# MotorController.net
KiCad netlist of a schematic drawn in Altium Designer
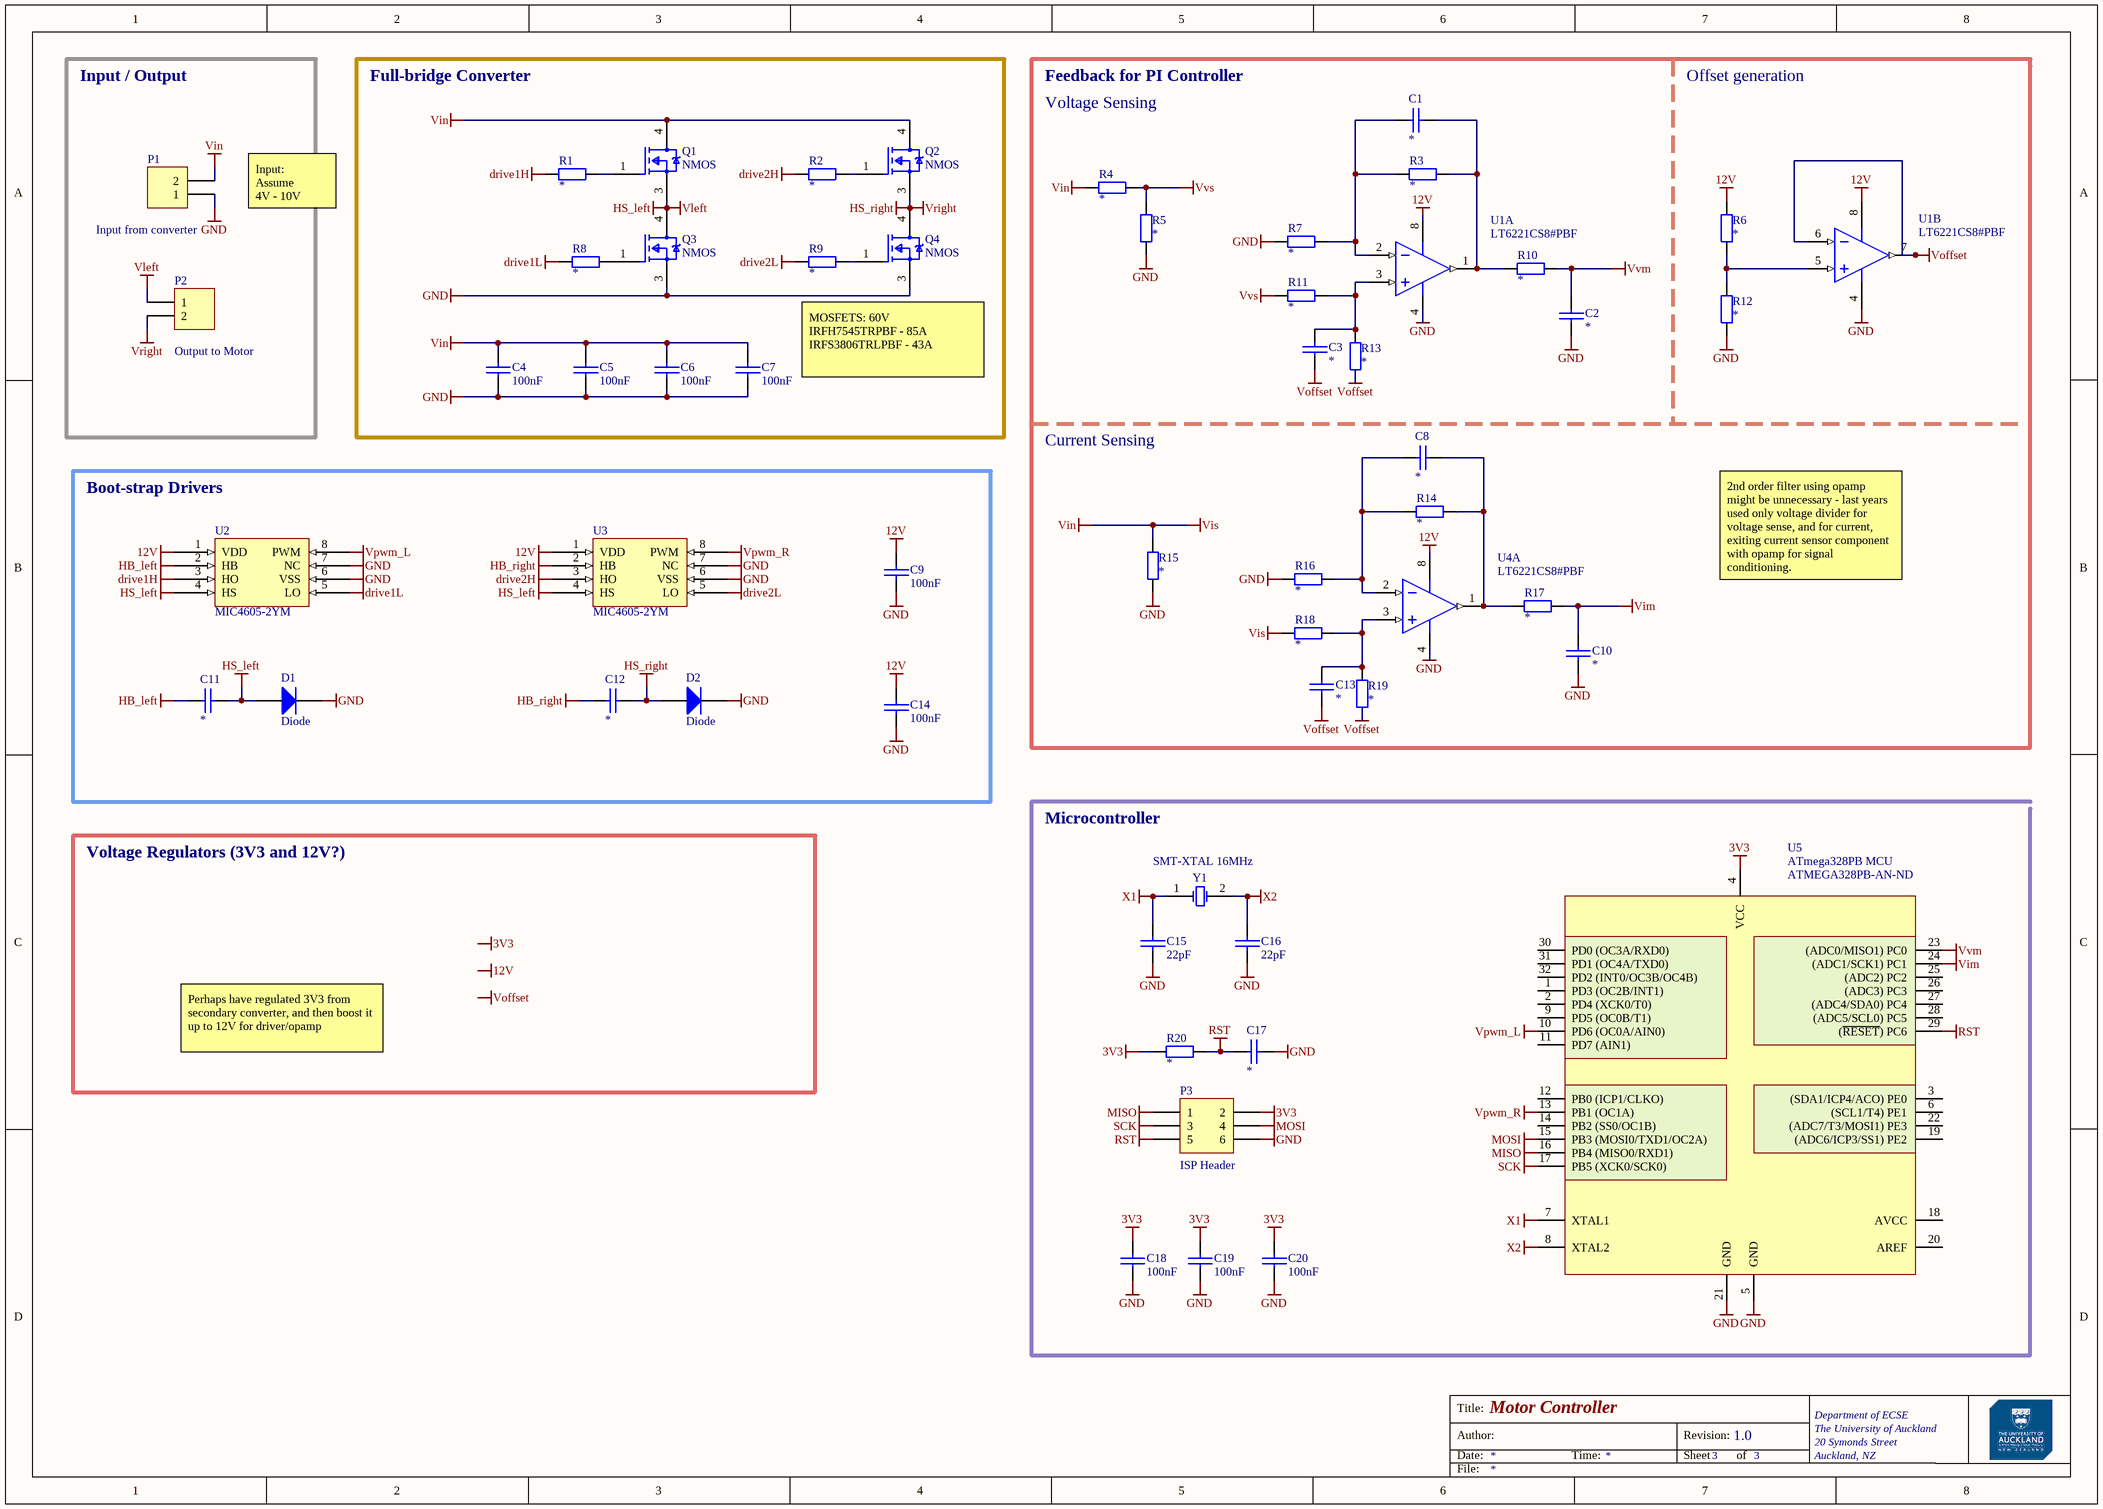
[diagram p0: MotorController.SchDoc]

(export (version "E")
  (design (tool "Eeschema 10.0.6"))
  (components
    (comp (ref "C1")
      (value "*")
      (footprint "0805 CAP")
      (description "SMT ceramic capacitor 0805 size")
      (libsource (lib "EE209_Library") (part "CerCap_SMT_0805"))
    )
    (comp (ref "C2")
      (value "*")
      (footprint "0805 CAP")
      (description "SMT ceramic capacitor 0805 size")
      (libsource (lib "EE209_Library") (part "CerCap_SMT_0805"))
    )
    (comp (ref "C3")
      (value "*")
      (footprint "0805 CAP")
      (description "SMT ceramic capacitor 0805 size")
      (libsource (lib "EE209_Library") (part "CerCap_SMT_0805"))
    )
    (comp (ref "C4")
      (value "100nF")
      (footprint "0805 CAP")
      (description "SMT ceramic capacitor 0805 size")
      (libsource (lib "EE209_Library") (part "CerCap_SMT_0805"))
    )
    (comp (ref "C5")
      (value "100nF")
      (footprint "0805 CAP")
      (description "SMT ceramic capacitor 0805 size")
      (libsource (lib "EE209_Library") (part "CerCap_SMT_0805"))
    )
    (comp (ref "C6")
      (value "100nF")
      (footprint "0805 CAP")
      (description "SMT ceramic capacitor 0805 size")
      (libsource (lib "EE209_Library") (part "CerCap_SMT_0805"))
    )
    (comp (ref "C7")
      (value "100nF")
      (footprint "0805 CAP")
      (description "SMT ceramic capacitor 0805 size")
      (libsource (lib "EE209_Library") (part "CerCap_SMT_0805"))
    )
    (comp (ref "C8")
      (value "*")
      (footprint "0805 CAP")
      (description "SMT ceramic capacitor 0805 size")
      (libsource (lib "EE209_Library") (part "CerCap_SMT_0805"))
    )
    (comp (ref "C9")
      (value "100nF")
      (footprint "0805 CAP")
      (description "SMT ceramic capacitor 0805 size")
      (libsource (lib "EE209_Library") (part "CerCap_SMT_0805"))
    )
    (comp (ref "C10")
      (value "*")
      (footprint "0805 CAP")
      (description "SMT ceramic capacitor 0805 size")
      (libsource (lib "EE209_Library") (part "CerCap_SMT_0805"))
    )
    (comp (ref "C11")
      (value "*")
      (footprint "0805 CAP")
      (description "SMT ceramic capacitor 0805 size")
      (libsource (lib "EE209_Library") (part "CerCap_SMT_0805"))
    )
    (comp (ref "C12")
      (value "*")
      (footprint "0805 CAP")
      (description "SMT ceramic capacitor 0805 size")
      (libsource (lib "EE209_Library") (part "CerCap_SMT_0805"))
    )
    (comp (ref "C13")
      (value "*")
      (footprint "0805 CAP")
      (description "SMT ceramic capacitor 0805 size")
      (libsource (lib "EE209_Library") (part "CerCap_SMT_0805"))
    )
    (comp (ref "C14")
      (value "100nF")
      (footprint "0805 CAP")
      (description "SMT ceramic capacitor 0805 size")
      (libsource (lib "EE209_Library") (part "CerCap_SMT_0805"))
    )
    (comp (ref "C15")
      (value "22pF")
      (footprint "0805 CAP")
      (description "SMT ceramic capacitor 0805 size")
      (libsource (lib "EE209_Library") (part "CerCap_SMT_0805"))
    )
    (comp (ref "C16")
      (value "22pF")
      (footprint "0805 CAP")
      (description "SMT ceramic capacitor 0805 size")
      (libsource (lib "EE209_Library") (part "CerCap_SMT_0805"))
    )
    (comp (ref "C17")
      (value "*")
      (footprint "0805 CAP")
      (description "SMT ceramic capacitor 0805 size")
      (libsource (lib "EE209_Library") (part "CerCap_SMT_0805"))
    )
    (comp (ref "C18")
      (value "100nF")
      (footprint "0805 CAP")
      (description "SMT ceramic capacitor 0805 size")
      (libsource (lib "EE209_Library") (part "CerCap_SMT_0805"))
    )
    (comp (ref "C19")
      (value "100nF")
      (footprint "0805 CAP")
      (description "SMT ceramic capacitor 0805 size")
      (libsource (lib "EE209_Library") (part "CerCap_SMT_0805"))
    )
    (comp (ref "C20")
      (value "100nF")
      (footprint "0805 CAP")
      (description "SMT ceramic capacitor 0805 size")
      (libsource (lib "EE209_Library") (part "CerCap_SMT_0805"))
    )
    (comp (ref "D1")
      (value "Diode")
      (footprint "SMC")
      (description "Default Diode")
      (fields (field (name "PUBLISHER") "Altium Limited"))
      (libsource (lib "Miscellaneous Devices") (part "Diode"))
    )
    (comp (ref "D2")
      (value "Diode")
      (footprint "SMC")
      (description "Default Diode")
      (fields (field (name "PUBLISHER") "Altium Limited"))
      (libsource (lib "Miscellaneous Devices") (part "Diode"))
    )
    (comp (ref "P1")
      (value "Input from converter")
      (footprint "HDR1X2H")
      (description "Header, 2-Pin, Right Angle")
      (fields (field (name "PUBLISHER") "Altium Limited"))
      (libsource (lib "Miscellaneous Connectors") (part "Header 2H"))
    )
    (comp (ref "P2")
      (value "Output to Motor")
      (footprint "HDR1X2H")
      (description "Header, 2-Pin, Right Angle")
      (fields (field (name "PUBLISHER") "Altium Limited"))
      (libsource (lib "") (part "Header 2H_1"))
    )
    (comp (ref "P3")
      (value "ISP Header")
      (footprint "HDR2X3")
      (description "Header, 3-Pin, Dual row")
      (fields (field (name "PUBLISHER") "Altium Limited"))
      (libsource (lib "Miscellaneous Connectors") (part "Header 3X2"))
    )
    (comp (ref "Q1")
      (value "NMOS")
      (footprint "IRFS3806TRLPBFCT-ND")
      (description "Single N-Channel 60V 15.8 mOhm 22 nC HEXFET® Power Mosfet - D2PAK")
      (fields
        (field (name "MANUFACTURER") "Infineon")
        (field (name "MANUFACTURER PART NUMBER") "IRFS3806TRLPBF")
      )
      (libsource (lib "SummerWorkshop") (part "NMOS"))
    )
    (comp (ref "Q2")
      (value "NMOS")
      (footprint "IRFS3806TRLPBFCT-ND")
      (description "Single N-Channel 60V 15.8 mOhm 22 nC HEXFET® Power Mosfet - D2PAK")
      (fields
        (field (name "MANUFACTURER") "Infineon")
        (field (name "MANUFACTURER PART NUMBER") "IRFS3806TRLPBF")
      )
      (libsource (lib "SummerWorkshop") (part "NMOS"))
    )
    (comp (ref "Q3")
      (value "NMOS")
      (footprint "IRFS3806TRLPBFCT-ND")
      (description "Single N-Channel 60V 15.8 mOhm 22 nC HEXFET® Power Mosfet - D2PAK")
      (fields
        (field (name "MANUFACTURER") "Infineon")
        (field (name "MANUFACTURER PART NUMBER") "IRFS3806TRLPBF")
      )
      (libsource (lib "SummerWorkshop") (part "NMOS"))
    )
    (comp (ref "Q4")
      (value "NMOS")
      (footprint "IRFS3806TRLPBFCT-ND")
      (description "Single N-Channel 60V 15.8 mOhm 22 nC HEXFET® Power Mosfet - D2PAK")
      (fields
        (field (name "MANUFACTURER") "Infineon")
        (field (name "MANUFACTURER PART NUMBER") "IRFS3806TRLPBF")
      )
      (libsource (lib "SummerWorkshop") (part "NMOS"))
    )
    (comp (ref "R1")
      (value "*")
      (footprint "0805 RES")
      (description "0805 resistor")
      (fields (field (name "PUBLISHER") "Altium Limited"))
      (libsource (lib "EE209_Library") (part "Res_SMT_0805"))
    )
    (comp (ref "R2")
      (value "*")
      (footprint "0805 RES")
      (description "0805 resistor")
      (fields (field (name "PUBLISHER") "Altium Limited"))
      (libsource (lib "EE209_Library") (part "Res_SMT_0805"))
    )
    (comp (ref "R3")
      (value "*")
      (footprint "0805 RES")
      (description "0805 resistor")
      (fields (field (name "PUBLISHER") "Altium Limited"))
      (libsource (lib "") (part "Res_SMT_0805_2"))
    )
    (comp (ref "R4")
      (value "*")
      (footprint "0805 RES")
      (description "0805 resistor")
      (fields (field (name "PUBLISHER") "Altium Limited"))
      (libsource (lib "") (part "Res_SMT_0805_2"))
    )
    (comp (ref "R5")
      (value "*")
      (footprint "0805 RES")
      (description "0805 resistor")
      (fields (field (name "PUBLISHER") "Altium Limited"))
      (libsource (lib "") (part "Res_SMT_0805_3"))
    )
    (comp (ref "R6")
      (value "*")
      (footprint "0805 RES")
      (description "0805 resistor")
      (fields (field (name "PUBLISHER") "Altium Limited"))
      (libsource (lib "") (part "Res_SMT_0805_1"))
    )
    (comp (ref "R7")
      (value "*")
      (footprint "0805 RES")
      (description "0805 resistor")
      (fields (field (name "PUBLISHER") "Altium Limited"))
      (libsource (lib "EE209_Library") (part "Res_SMT_0805"))
    )
    (comp (ref "R8")
      (value "*")
      (footprint "0805 RES")
      (description "0805 resistor")
      (fields (field (name "PUBLISHER") "Altium Limited"))
      (libsource (lib "EE209_Library") (part "Res_SMT_0805"))
    )
    (comp (ref "R9")
      (value "*")
      (footprint "0805 RES")
      (description "0805 resistor")
      (fields (field (name "PUBLISHER") "Altium Limited"))
      (libsource (lib "EE209_Library") (part "Res_SMT_0805"))
    )
    (comp (ref "R10")
      (value "*")
      (footprint "0805 RES")
      (description "0805 resistor")
      (fields (field (name "PUBLISHER") "Altium Limited"))
      (libsource (lib "") (part "Res_SMT_0805_2"))
    )
    (comp (ref "R11")
      (value "*")
      (footprint "0805 RES")
      (description "0805 resistor")
      (fields (field (name "PUBLISHER") "Altium Limited"))
      (libsource (lib "EE209_Library") (part "Res_SMT_0805"))
    )
    (comp (ref "R12")
      (value "*")
      (footprint "0805 RES")
      (description "0805 resistor")
      (fields (field (name "PUBLISHER") "Altium Limited"))
      (libsource (lib "") (part "Res_SMT_0805_1"))
    )
    (comp (ref "R13")
      (value "*")
      (footprint "0805 RES")
      (description "0805 resistor")
      (fields (field (name "PUBLISHER") "Altium Limited"))
      (libsource (lib "") (part "Res_SMT_0805_1"))
    )
    (comp (ref "R14")
      (value "*")
      (footprint "0805 RES")
      (description "0805 resistor")
      (fields (field (name "PUBLISHER") "Altium Limited"))
      (libsource (lib "") (part "Res_SMT_0805_2"))
    )
    (comp (ref "R15")
      (value "*")
      (footprint "0805 RES")
      (description "0805 resistor")
      (fields (field (name "PUBLISHER") "Altium Limited"))
      (libsource (lib "") (part "Res_SMT_0805_3"))
    )
    (comp (ref "R16")
      (value "*")
      (footprint "0805 RES")
      (description "0805 resistor")
      (fields (field (name "PUBLISHER") "Altium Limited"))
      (libsource (lib "EE209_Library") (part "Res_SMT_0805"))
    )
    (comp (ref "R17")
      (value "*")
      (footprint "0805 RES")
      (description "0805 resistor")
      (fields (field (name "PUBLISHER") "Altium Limited"))
      (libsource (lib "") (part "Res_SMT_0805_2"))
    )
    (comp (ref "R18")
      (value "*")
      (footprint "0805 RES")
      (description "0805 resistor")
      (fields (field (name "PUBLISHER") "Altium Limited"))
      (libsource (lib "EE209_Library") (part "Res_SMT_0805"))
    )
    (comp (ref "R19")
      (value "*")
      (footprint "0805 RES")
      (description "0805 resistor")
      (fields (field (name "PUBLISHER") "Altium Limited"))
      (libsource (lib "") (part "Res_SMT_0805_1"))
    )
    (comp (ref "R20")
      (value "*")
      (footprint "0805 RES")
      (description "0805 resistor")
      (fields (field (name "PUBLISHER") "Altium Limited"))
      (libsource (lib "") (part "Res_SMT_0805_2"))
    )
    (comp (ref "U1")
      (value "LT6221CS8#PBF")
      (footprint "LT-S8-8_N")
      (fields
        (field (name "LINEAR TECHNOLOGY PART NUMBER") "LT6221")
        (field (name "MANUFACTURER") "Linear Technology")
      )
      (libsource (lib "Altium Content Vault") (part "LT-LT6221-S8-8"))
    )
    (comp (ref "U2")
      (value "MIC4605-2YM")
      (description "Driver 1A 2-OUT High and Low Side Half Brdg Non-Inv 8-Pin SOIC N Tube")
      (fields
        (field (name "MANUFACTURER") "Microchip")
        (field (name "MANUFACTURER PART NUMBER") "MIC4605-2YM-T5")
      )
      (libsource (lib "SummerWorkshop") (part "MIC4605-2YM"))
    )
    (comp (ref "U3")
      (value "MIC4605-2YM")
      (description "Driver 1A 2-OUT High and Low Side Half Brdg Non-Inv 8-Pin SOIC N Tube")
      (fields
        (field (name "MANUFACTURER") "Microchip")
        (field (name "MANUFACTURER PART NUMBER") "MIC4605-2YM-T5")
      )
      (libsource (lib "SummerWorkshop") (part "MIC4605-2YM"))
    )
    (comp (ref "U4")
      (value "LT6221CS8#PBF")
      (footprint "LT-S8-8_N")
      (fields
        (field (name "LINEAR TECHNOLOGY PART NUMBER") "LT6221")
        (field (name "MANUFACTURER") "Linear Technology")
      )
      (libsource (lib "Altium Content Vault") (part "LT-LT6221-S8-8"))
    )
    (comp (ref "U5")
      (value "ATmega328PB MCU")
      (footprint "32 - TQFP")
      (description "IC MCU 8BIT 32KB FLASH 32TQFP")
      (fields
        (field (name "MANUFACTURER") "Atmel")
        (field (name "MANUFACTURER PART NUMBER") "ATMEGA328PB-AN")
        (field (name "SUPPLIER PART NUMBER 1") "ATMEGA328PB-AN-ND")
      )
      (libsource (lib "EE209_Library") (part "ATmega328PB_SMT_TQFP32"))
    )
    (comp (ref "Y1")
      (value "SMT-XTAL 16MHz")
      (footprint "HC49-US")
      (description "9C-16.000MAAJ-T crystal 16.0000MHZ 18PF SMD")
      (fields
        (field (name "MANUFACTURER") "TXC CORPORATION")
        (field (name "MANUFACTURER PART NUMBER") "9C-16.000MAAJ-T")
      )
      (libsource (lib "EE209_Library") (part "TXC9C-16_XTAL_SMT"))
    )
  )
  (nets
    (net (code "1") (name "3V3") (class "Default")
      (node (ref "C18") (pin "1") (pinfunction "1_1") (pintype "passive"))
      (node (ref "C19") (pin "1") (pinfunction "1_1") (pintype "passive"))
      (node (ref "C20") (pin "1") (pinfunction "1_1") (pintype "passive"))
      (node (ref "P3") (pin "2") (pinfunction "2_2") (pintype "passive"))
      (node (ref "R20") (pin "2") (pinfunction "2_2") (pintype "passive"))
      (node (ref "U5") (pin "4") (pinfunction "VCC_4") (pintype "passive"))
    )
    (net (code "2") (name "12V") (class "Default")
      (node (ref "C14") (pin "2") (pinfunction "2_2") (pintype "passive"))
      (node (ref "C9") (pin "2") (pinfunction "2_2") (pintype "passive"))
      (node (ref "R6") (pin "2") (pinfunction "2_2") (pintype "passive"))
      (node (ref "U1") (pin "8") (pinfunction "VS+_8") (pintype "power_in"))
      (node (ref "U2") (pin "1") (pinfunction "VDD_1") (pintype "input"))
      (node (ref "U3") (pin "1") (pinfunction "VDD_1") (pintype "input"))
      (node (ref "U4") (pin "8") (pinfunction "VS+_8") (pintype "power_in"))
    )
    (net (code "3") (name "GND") (class "Default")
      (node (ref "C10") (pin "1") (pinfunction "1_1") (pintype "passive"))
      (node (ref "C14") (pin "1") (pinfunction "1_1") (pintype "passive"))
      (node (ref "C15") (pin "2") (pinfunction "2_2") (pintype "passive"))
      (node (ref "C16") (pin "2") (pinfunction "2_2") (pintype "passive"))
      (node (ref "C17") (pin "2") (pinfunction "2_2") (pintype "passive"))
      (node (ref "C18") (pin "2") (pinfunction "2_2") (pintype "passive"))
      (node (ref "C19") (pin "2") (pinfunction "2_2") (pintype "passive"))
      (node (ref "C2") (pin "1") (pinfunction "1_1") (pintype "passive"))
      (node (ref "C20") (pin "2") (pinfunction "2_2") (pintype "passive"))
      (node (ref "C4") (pin "1") (pinfunction "1_1") (pintype "passive"))
      (node (ref "C5") (pin "1") (pinfunction "1_1") (pintype "passive"))
      (node (ref "C6") (pin "1") (pinfunction "1_1") (pintype "passive"))
      (node (ref "C7") (pin "1") (pinfunction "1_1") (pintype "passive"))
      (node (ref "C9") (pin "1") (pinfunction "1_1") (pintype "passive"))
      (node (ref "D1") (pin "2") (pinfunction "K_2") (pintype "passive"))
      (node (ref "D2") (pin "2") (pinfunction "K_2") (pintype "passive"))
      (node (ref "P1") (pin "1") (pinfunction "1_1") (pintype "passive"))
      (node (ref "P3") (pin "6") (pinfunction "6_6") (pintype "passive"))
      (node (ref "Q3") (pin "3") (pinfunction "S_3") (pintype "passive"))
      (node (ref "Q4") (pin "3") (pinfunction "S_3") (pintype "passive"))
      (node (ref "R12") (pin "1") (pinfunction "1_1") (pintype "passive"))
      (node (ref "R15") (pin "2") (pinfunction "2_2") (pintype "passive"))
      (node (ref "R16") (pin "1") (pinfunction "1_1") (pintype "passive"))
      (node (ref "R5") (pin "2") (pinfunction "2_2") (pintype "passive"))
      (node (ref "R7") (pin "1") (pinfunction "1_1") (pintype "passive"))
      (node (ref "U1") (pin "4") (pinfunction "VS-_4") (pintype "power_in"))
      (node (ref "U2") (pin "6") (pinfunction "VSS_6") (pintype "input"))
      (node (ref "U2") (pin "7") (pinfunction "NC_7") (pintype "input"))
      (node (ref "U3") (pin "6") (pinfunction "VSS_6") (pintype "input"))
      (node (ref "U3") (pin "7") (pinfunction "NC_7") (pintype "input"))
      (node (ref "U4") (pin "4") (pinfunction "VS-_4") (pintype "power_in"))
      (node (ref "U5") (pin "21") (pinfunction "GND_21") (pintype "passive"))
      (node (ref "U5") (pin "5") (pinfunction "GND_5") (pintype "passive"))
    )
    (net (code "4") (name "HB_left") (class "Default")
      (node (ref "C11") (pin "1") (pinfunction "1_1") (pintype "passive"))
      (node (ref "U2") (pin "2") (pinfunction "HB_2") (pintype "input"))
    )
    (net (code "5") (name "HB_right") (class "Default")
      (node (ref "C12") (pin "1") (pinfunction "1_1") (pintype "passive"))
      (node (ref "U3") (pin "2") (pinfunction "HB_2") (pintype "input"))
    )
    (net (code "6") (name "HS_left") (class "Default")
      (node (ref "C11") (pin "2") (pinfunction "2_2") (pintype "passive"))
      (node (ref "D1") (pin "1") (pinfunction "A_1") (pintype "passive"))
      (node (ref "P2") (pin "1") (pinfunction "1_1") (pintype "passive"))
      (node (ref "Q1") (pin "3") (pinfunction "S_3") (pintype "passive"))
      (node (ref "Q3") (pin "4") (pinfunction "D_4") (pintype "passive"))
      (node (ref "U2") (pin "4") (pinfunction "HS_4") (pintype "input"))
      (node (ref "U3") (pin "4") (pinfunction "HS_4") (pintype "input"))
    )
    (net (code "7") (name "HS_right") (class "Default")
      (node (ref "C12") (pin "2") (pinfunction "2_2") (pintype "passive"))
      (node (ref "D2") (pin "1") (pinfunction "A_1") (pintype "passive"))
      (node (ref "P2") (pin "2") (pinfunction "2_2") (pintype "passive"))
      (node (ref "Q2") (pin "3") (pinfunction "S_3") (pintype "passive"))
      (node (ref "Q4") (pin "4") (pinfunction "D_4") (pintype "passive"))
    )
    (net (code "8") (name "MISO") (class "Default")
      (node (ref "P3") (pin "1") (pinfunction "1_1") (pintype "passive"))
      (node (ref "U5") (pin "16") (pinfunction "PB4_(MISO0/RXD1)_16") (pintype "passive"))
    )
    (net (code "9") (name "MOSI") (class "Default")
      (node (ref "P3") (pin "4") (pinfunction "4_4") (pintype "passive"))
      (node (ref "U5") (pin "15") (pinfunction "PB3_(MOSI0/TXD1/OC2A)_15") (pintype "passive"))
    )
    (net (code "10") (name "Net-(Q1-G)") (class "Default")
      (node (ref "Q1") (pin "1") (pinfunction "G_1") (pintype "passive"))
      (node (ref "R1") (pin "2") (pinfunction "2_2") (pintype "passive"))
    )
    (net (code "11") (name "Net-(Q2-G)") (class "Default")
      (node (ref "Q2") (pin "1") (pinfunction "G_1") (pintype "passive"))
      (node (ref "R2") (pin "2") (pinfunction "2_2") (pintype "passive"))
    )
    (net (code "12") (name "Net-(Q3-G)") (class "Default")
      (node (ref "Q3") (pin "1") (pinfunction "G_1") (pintype "passive"))
      (node (ref "R8") (pin "2") (pinfunction "2_2") (pintype "passive"))
    )
    (net (code "13") (name "Net-(Q4-G)") (class "Default")
      (node (ref "Q4") (pin "1") (pinfunction "G_1") (pintype "passive"))
      (node (ref "R9") (pin "2") (pinfunction "2_2") (pintype "passive"))
    )
    (net (code "14") (name "Net-(U1A-+IN_A)") (class "Default")
      (node (ref "C3") (pin "2") (pinfunction "2_2") (pintype "passive"))
      (node (ref "R11") (pin "2") (pinfunction "2_2") (pintype "passive"))
      (node (ref "R13") (pin "2") (pinfunction "2_2") (pintype "passive"))
      (node (ref "U1") (pin "3") (pinfunction "+IN_A_3") (pintype "input"))
    )
    (net (code "15") (name "Net-(U1A--IN_A)") (class "Default")
      (node (ref "C1") (pin "1") (pinfunction "1_1") (pintype "passive"))
      (node (ref "R3") (pin "2") (pinfunction "2_2") (pintype "passive"))
      (node (ref "R7") (pin "2") (pinfunction "2_2") (pintype "passive"))
      (node (ref "U1") (pin "2") (pinfunction "-IN_A_2") (pintype "input"))
    )
    (net (code "16") (name "Net-(U1A-OUT_A)") (class "Default")
      (node (ref "C1") (pin "2") (pinfunction "2_2") (pintype "passive"))
      (node (ref "R10") (pin "2") (pinfunction "2_2") (pintype "passive"))
      (node (ref "R3") (pin "1") (pinfunction "1_1") (pintype "passive"))
      (node (ref "U1") (pin "1") (pinfunction "OUT_A_1") (pintype "output"))
    )
    (net (code "17") (name "Net-(U1B-+IN_B)") (class "Default")
      (node (ref "R12") (pin "2") (pinfunction "2_2") (pintype "passive"))
      (node (ref "R6") (pin "1") (pinfunction "1_1") (pintype "passive"))
      (node (ref "U1") (pin "5") (pinfunction "+IN_B_5") (pintype "input"))
    )
    (net (code "18") (name "Net-(U4A-+IN_A)") (class "Default")
      (node (ref "C13") (pin "2") (pinfunction "2_2") (pintype "passive"))
      (node (ref "R18") (pin "2") (pinfunction "2_2") (pintype "passive"))
      (node (ref "R19") (pin "2") (pinfunction "2_2") (pintype "passive"))
      (node (ref "U4") (pin "3") (pinfunction "+IN_A_3") (pintype "input"))
    )
    (net (code "19") (name "Net-(U4A--IN_A)") (class "Default")
      (node (ref "C8") (pin "1") (pinfunction "1_1") (pintype "passive"))
      (node (ref "R14") (pin "2") (pinfunction "2_2") (pintype "passive"))
      (node (ref "R16") (pin "2") (pinfunction "2_2") (pintype "passive"))
      (node (ref "U4") (pin "2") (pinfunction "-IN_A_2") (pintype "input"))
    )
    (net (code "20") (name "Net-(U4A-OUT_A)") (class "Default")
      (node (ref "C8") (pin "2") (pinfunction "2_2") (pintype "passive"))
      (node (ref "R14") (pin "1") (pinfunction "1_1") (pintype "passive"))
      (node (ref "R17") (pin "2") (pinfunction "2_2") (pintype "passive"))
      (node (ref "U4") (pin "1") (pinfunction "OUT_A_1") (pintype "output"))
    )
    (net (code "21") (name "RST") (class "Default")
      (node (ref "C17") (pin "1") (pinfunction "1_1") (pintype "passive"))
      (node (ref "P3") (pin "5") (pinfunction "5_5") (pintype "passive"))
      (node (ref "R20") (pin "1") (pinfunction "1_1") (pintype "passive"))
      (node (ref "U5") (pin "29") (pinfunction "(~{RESET})_PC6_29") (pintype "passive"))
    )
    (net (code "22") (name "SCK") (class "Default")
      (node (ref "P3") (pin "3") (pinfunction "3_3") (pintype "passive"))
      (node (ref "U5") (pin "17") (pinfunction "PB5_(XCK0/SCK0)_17") (pintype "passive"))
    )
    (net (code "23") (name "Vim") (class "Default")
      (node (ref "C10") (pin "2") (pinfunction "2_2") (pintype "passive"))
      (node (ref "R17") (pin "1") (pinfunction "1_1") (pintype "passive"))
      (node (ref "U5") (pin "24") (pinfunction "(ADC1/SCK1)_PC1_24") (pintype "passive"))
    )
    (net (code "24") (name "Vin") (class "Default")
      (node (ref "C4") (pin "2") (pinfunction "2_2") (pintype "passive"))
      (node (ref "C5") (pin "2") (pinfunction "2_2") (pintype "passive"))
      (node (ref "C6") (pin "2") (pinfunction "2_2") (pintype "passive"))
      (node (ref "C7") (pin "2") (pinfunction "2_2") (pintype "passive"))
      (node (ref "P1") (pin "2") (pinfunction "2_2") (pintype "passive"))
      (node (ref "Q1") (pin "4") (pinfunction "D_4") (pintype "passive"))
      (node (ref "Q2") (pin "4") (pinfunction "D_4") (pintype "passive"))
      (node (ref "R15") (pin "1") (pinfunction "1_1") (pintype "passive"))
      (node (ref "R18") (pin "1") (pinfunction "1_1") (pintype "passive"))
      (node (ref "R4") (pin "2") (pinfunction "2_2") (pintype "passive"))
    )
    (net (code "25") (name "Voffset") (class "Default")
      (node (ref "C13") (pin "1") (pinfunction "1_1") (pintype "passive"))
      (node (ref "C3") (pin "1") (pinfunction "1_1") (pintype "passive"))
      (node (ref "R13") (pin "1") (pinfunction "1_1") (pintype "passive"))
      (node (ref "R19") (pin "1") (pinfunction "1_1") (pintype "passive"))
      (node (ref "U1") (pin "6") (pinfunction "-IN_B_6") (pintype "input"))
      (node (ref "U1") (pin "7") (pinfunction "OUT_B_7") (pintype "output"))
    )
    (net (code "26") (name "Vpwm_L") (class "Default")
      (node (ref "U2") (pin "8") (pinfunction "PWM_8") (pintype "input"))
      (node (ref "U5") (pin "10") (pinfunction "PD6_(OC0A/AIN0)_10") (pintype "passive"))
    )
    (net (code "27") (name "Vpwm_R") (class "Default")
      (node (ref "U3") (pin "8") (pinfunction "PWM_8") (pintype "input"))
      (node (ref "U5") (pin "13") (pinfunction "PB1_(OC1A)_13") (pintype "passive"))
    )
    (net (code "28") (name "Vvm") (class "Default")
      (node (ref "C2") (pin "2") (pinfunction "2_2") (pintype "passive"))
      (node (ref "R10") (pin "1") (pinfunction "1_1") (pintype "passive"))
      (node (ref "U5") (pin "23") (pinfunction "(ADC0/MISO1)_PC0_23") (pintype "passive"))
    )
    (net (code "29") (name "Vvs") (class "Default")
      (node (ref "R11") (pin "1") (pinfunction "1_1") (pintype "passive"))
      (node (ref "R4") (pin "1") (pinfunction "1_1") (pintype "passive"))
      (node (ref "R5") (pin "1") (pinfunction "1_1") (pintype "passive"))
    )
    (net (code "30") (name "X1") (class "Default")
      (node (ref "C15") (pin "1") (pinfunction "1_1") (pintype "passive"))
      (node (ref "U5") (pin "7") (pinfunction "XTAL1_7") (pintype "passive"))
      (node (ref "Y1") (pin "1") (pinfunction "OSC1_1") (pintype "passive"))
    )
    (net (code "31") (name "X2") (class "Default")
      (node (ref "C16") (pin "1") (pinfunction "1_1") (pintype "passive"))
      (node (ref "U5") (pin "8") (pinfunction "XTAL2_8") (pintype "passive"))
      (node (ref "Y1") (pin "2") (pinfunction "OSC2_2") (pintype "passive"))
    )
    (net (code "32") (name "drive1H") (class "Default")
      (node (ref "R1") (pin "1") (pinfunction "1_1") (pintype "passive"))
      (node (ref "U2") (pin "3") (pinfunction "HO_3") (pintype "input"))
    )
    (net (code "33") (name "drive1L") (class "Default")
      (node (ref "R8") (pin "1") (pinfunction "1_1") (pintype "passive"))
      (node (ref "U2") (pin "5") (pinfunction "LO_5") (pintype "input"))
    )
    (net (code "34") (name "drive2H") (class "Default")
      (node (ref "R2") (pin "1") (pinfunction "1_1") (pintype "passive"))
      (node (ref "U3") (pin "3") (pinfunction "HO_3") (pintype "input"))
    )
    (net (code "35") (name "drive2L") (class "Default")
      (node (ref "R9") (pin "1") (pinfunction "1_1") (pintype "passive"))
      (node (ref "U3") (pin "5") (pinfunction "LO_5") (pintype "input"))
    )
    (net (code "36") (name "unconnected-(U5-(ADC2)_PC2-Pad25)") (class "Default")
      (node (ref "U5") (pin "25") (pinfunction "(ADC2)_PC2_25") (pintype "passive"))
    )
    (net (code "37") (name "unconnected-(U5-(ADC3)_PC3-Pad26)") (class "Default")
      (node (ref "U5") (pin "26") (pinfunction "(ADC3)_PC3_26") (pintype "passive"))
    )
    (net (code "38") (name "unconnected-(U5-(ADC4{slash}SDA0)_PC4-Pad27)") (class "Default")
      (node (ref "U5") (pin "27") (pinfunction "(ADC4/SDA0)_PC4_27") (pintype "passive"))
    )
    (net (code "39") (name "unconnected-(U5-(ADC5{slash}SCL0)_PC5-Pad28)") (class "Default")
      (node (ref "U5") (pin "28") (pinfunction "(ADC5/SCL0)_PC5_28") (pintype "passive"))
    )
    (net (code "40") (name "unconnected-(U5-(ADC6{slash}ICP3{slash}SS1)_PE2-Pad19)") (class "Default")
      (node (ref "U5") (pin "19") (pinfunction "(ADC6/ICP3/SS1)_PE2_19") (pintype "passive"))
    )
    (net (code "41") (name "unconnected-(U5-(ADC7{slash}T3{slash}MOSI1)_PE3-Pad22)") (class "Default")
      (node (ref "U5") (pin "22") (pinfunction "(ADC7/T3/MOSI1)_PE3_22") (pintype "passive"))
    )
    (net (code "42") (name "unconnected-(U5-(SCL1{slash}T4)_PE1-Pad6)") (class "Default")
      (node (ref "U5") (pin "6") (pinfunction "(SCL1/T4)_PE1_6") (pintype "passive"))
    )
    (net (code "43") (name "unconnected-(U5-(SDA1{slash}ICP4{slash}ACO)_PE0-Pad3)") (class "Default")
      (node (ref "U5") (pin "3") (pinfunction "(SDA1/ICP4/ACO)_PE0_3") (pintype "passive"))
    )
    (net (code "44") (name "unconnected-(U5-AREF-Pad20)") (class "Default")
      (node (ref "U5") (pin "20") (pinfunction "AREF_20") (pintype "passive"))
    )
    (net (code "45") (name "unconnected-(U5-AVCC-Pad18)") (class "Default")
      (node (ref "U5") (pin "18") (pinfunction "AVCC_18") (pintype "passive"))
    )
    (net (code "46") (name "unconnected-(U5-PB0_(ICP1{slash}CLKO)-Pad12)") (class "Default")
      (node (ref "U5") (pin "12") (pinfunction "PB0_(ICP1/CLKO)_12") (pintype "passive"))
    )
    (net (code "47") (name "unconnected-(U5-PB2_(SS0{slash}OC1B)-Pad14)") (class "Default")
      (node (ref "U5") (pin "14") (pinfunction "PB2_(SS0/OC1B)_14") (pintype "passive"))
    )
    (net (code "48") (name "unconnected-(U5-PD0_(OC3A{slash}RXD0)-Pad30)") (class "Default")
      (node (ref "U5") (pin "30") (pinfunction "PD0_(OC3A/RXD0)_30") (pintype "passive"))
    )
    (net (code "49") (name "unconnected-(U5-PD1_(OC4A{slash}TXD0)-Pad31)") (class "Default")
      (node (ref "U5") (pin "31") (pinfunction "PD1_(OC4A/TXD0)_31") (pintype "passive"))
    )
    (net (code "50") (name "unconnected-(U5-PD2_(INT0{slash}OC3B{slash}OC4B)-Pad32)") (class "Default")
      (node (ref "U5") (pin "32") (pinfunction "PD2_(INT0/OC3B/OC4B)_32") (pintype "passive"))
    )
    (net (code "51") (name "unconnected-(U5-PD3_(OC2B{slash}INT1)-Pad1)") (class "Default")
      (node (ref "U5") (pin "1") (pinfunction "PD3_(OC2B/INT1)_1") (pintype "passive"))
    )
    (net (code "52") (name "unconnected-(U5-PD4_(XCK0{slash}T0)-Pad2)") (class "Default")
      (node (ref "U5") (pin "2") (pinfunction "PD4_(XCK0/T0)_2") (pintype "passive"))
    )
    (net (code "53") (name "unconnected-(U5-PD5_(OC0B{slash}T1)-Pad9)") (class "Default")
      (node (ref "U5") (pin "9") (pinfunction "PD5_(OC0B/T1)_9") (pintype "passive"))
    )
    (net (code "54") (name "unconnected-(U5-PD7_(AIN1)-Pad11)") (class "Default")
      (node (ref "U5") (pin "11") (pinfunction "PD7_(AIN1)_11") (pintype "passive"))
    )
  )
)
